# InputOutput.net
KiCad netlist of a schematic drawn in Altium Designer
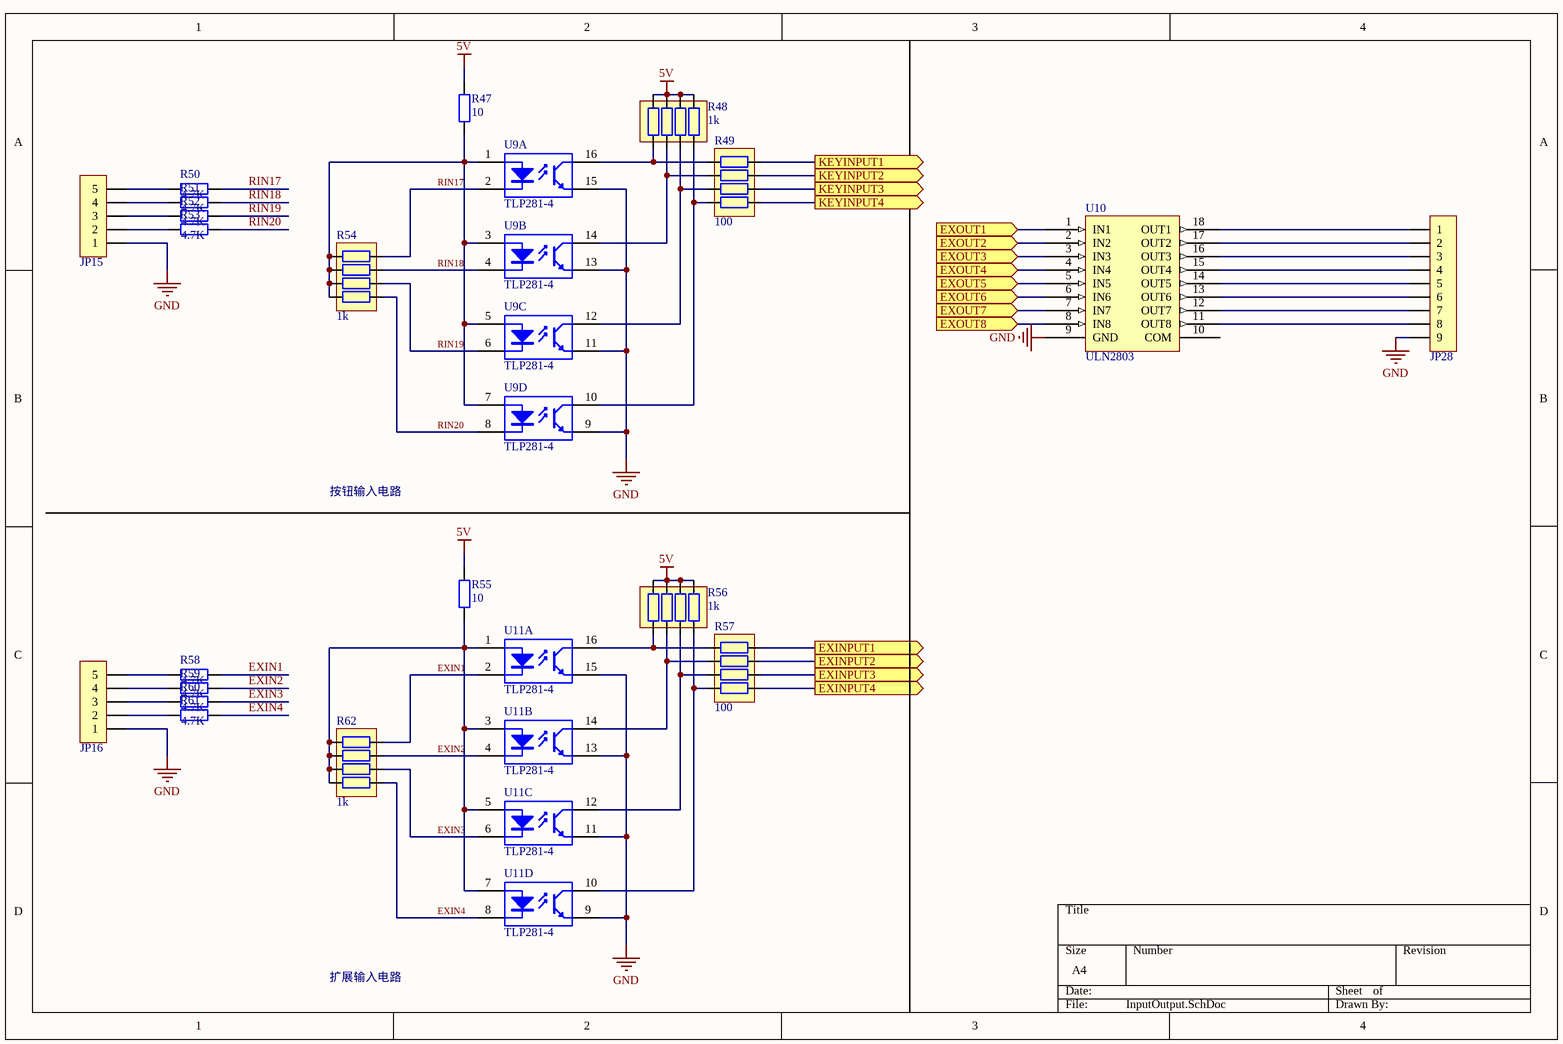
[diagram p0: InputOutput.SchDoc]

(export (version "E")
  (design (tool "Eeschema 10.0.6"))
  (components
    (comp (ref "JP15")
      (value "HDR-1X5")
      (footprint "XH2.54-LI-5P")
      (description "5P接插件")
      (libsource (lib "4.5   - 接插件-脚距2.54") (part "Header 5"))
    )
    (comp (ref "JP16")
      (value "HDR-1X5")
      (footprint "XH2.54-LI-5P")
      (description "5P接插件")
      (libsource (lib "4.5   - 接插件-脚距2.54") (part "Header 5"))
    )
    (comp (ref "JP28")
      (value "HDR-1X9")
      (footprint "XH2.54-LI-9P")
      (description "9P接插件")
      (libsource (lib "4.5   - 接插件-脚距2.54") (part "Header 9"))
    )
    (comp (ref "R47")
      (value "10")
      (footprint "R 0603_L")
      (description "贴片电阻")
      (libsource (lib "3.1   - 电阻-电容-电感") (part "R"))
    )
    (comp (ref "R48")
      (value "1k")
      (footprint "RCA-8P4R-0603")
      (description "贴片网络排阻")
      (libsource (lib "电阻-电容-电感") (part "R-8P4R"))
    )
    (comp (ref "R49")
      (value "100")
      (footprint "RCA-8P4R-0603")
      (description "贴片网络排阻")
      (libsource (lib "") (part "R-8P4R_1"))
    )
    (comp (ref "R50")
      (value "4.7K")
      (footprint "R 0603_L")
      (description "贴片电阻")
      (libsource (lib "3.1   - 电阻-电容-电感") (part "R"))
    )
    (comp (ref "R51")
      (value "4.7K")
      (footprint "R 0603_L")
      (description "贴片电阻")
      (libsource (lib "3.1   - 电阻-电容-电感") (part "R"))
    )
    (comp (ref "R52")
      (value "4.7K")
      (footprint "R 0603_L")
      (description "贴片电阻")
      (libsource (lib "3.1   - 电阻-电容-电感") (part "R"))
    )
    (comp (ref "R53")
      (value "4.7K")
      (footprint "R 0603_L")
      (description "贴片电阻")
      (libsource (lib "3.1   - 电阻-电容-电感") (part "R"))
    )
    (comp (ref "R54")
      (value "1k")
      (footprint "RCA-8P4R-0603")
      (description "贴片网络排阻")
      (libsource (lib "") (part "R-8P4R_2"))
    )
    (comp (ref "R55")
      (value "10")
      (footprint "R 0603_L")
      (description "贴片电阻")
      (libsource (lib "3.1   - 电阻-电容-电感") (part "R"))
    )
    (comp (ref "R56")
      (value "1k")
      (footprint "RCA-8P4R-0603")
      (description "贴片网络排阻")
      (libsource (lib "电阻-电容-电感") (part "R-8P4R"))
    )
    (comp (ref "R57")
      (value "100")
      (footprint "RCA-8P4R-0603")
      (description "贴片网络排阻")
      (libsource (lib "") (part "R-8P4R_1"))
    )
    (comp (ref "R58")
      (value "4.7K")
      (footprint "R 0603_L")
      (description "贴片电阻")
      (libsource (lib "3.1   - 电阻-电容-电感") (part "R"))
    )
    (comp (ref "R59")
      (value "4.7K")
      (footprint "R 0603_L")
      (description "贴片电阻")
      (libsource (lib "3.1   - 电阻-电容-电感") (part "R"))
    )
    (comp (ref "R60")
      (value "4.7K")
      (footprint "R 0603_L")
      (description "贴片电阻")
      (libsource (lib "3.1   - 电阻-电容-电感") (part "R"))
    )
    (comp (ref "R61")
      (value "4.7K")
      (footprint "R 0603_L")
      (description "贴片电阻")
      (libsource (lib "3.1   - 电阻-电容-电感") (part "R"))
    )
    (comp (ref "R62")
      (value "1k")
      (footprint "RCA-8P4R-0603")
      (description "贴片网络排阻")
      (libsource (lib "") (part "R-8P4R_2"))
    )
    (comp (ref "U9") (value "TLP281-4") (footprint "SOP16N_N") (libsource (lib "自编原件库") (part "TLP281-4")))
    (comp (ref "U10") (value "ULN2803") (footprint "SO-G18") (libsource (lib "总图") (part "ULN2803")))
    (comp (ref "U11") (value "TLP281-4") (footprint "SOP16N_N") (libsource (lib "自编原件库") (part "TLP281-4")))
  )
  (nets
    (net (code "1") (name "/EXIN1") (class "Default")
      (node (ref "R58") (pin "1") (pinfunction "1_1") (pintype "passive"))
      (node (ref "R62") (pin "8") (pinfunction "8_8") (pintype "passive"))
      (node (ref "U11") (pin "2") (pinfunction "2_2") (pintype "passive"))
    )
    (net (code "2") (name "/EXIN2") (class "Default")
      (node (ref "R59") (pin "1") (pinfunction "1_1") (pintype "passive"))
      (node (ref "R62") (pin "7") (pinfunction "7_7") (pintype "passive"))
      (node (ref "U11") (pin "4") (pinfunction "4_4") (pintype "passive"))
    )
    (net (code "3") (name "/EXIN3") (class "Default")
      (node (ref "R60") (pin "1") (pinfunction "1_1") (pintype "passive"))
      (node (ref "R62") (pin "6") (pinfunction "6_6") (pintype "passive"))
      (node (ref "U11") (pin "6") (pinfunction "6_6") (pintype "passive"))
    )
    (net (code "4") (name "/EXIN4") (class "Default")
      (node (ref "R61") (pin "1") (pinfunction "1_1") (pintype "passive"))
      (node (ref "R62") (pin "5") (pinfunction "5_5") (pintype "passive"))
      (node (ref "U11") (pin "8") (pinfunction "8_8") (pintype "passive"))
    )
    (net (code "5") (name "/EXINPUT1") (class "Default")
      (node (ref "R57") (pin "1") (pinfunction "1_1") (pintype "passive"))
    )
    (net (code "6") (name "/EXINPUT2") (class "Default")
      (node (ref "R57") (pin "2") (pinfunction "2_2") (pintype "passive"))
    )
    (net (code "7") (name "/EXINPUT3") (class "Default")
      (node (ref "R57") (pin "3") (pinfunction "3_3") (pintype "passive"))
    )
    (net (code "8") (name "/EXINPUT4") (class "Default")
      (node (ref "R57") (pin "4") (pinfunction "4_4") (pintype "passive"))
    )
    (net (code "9") (name "/EXOUT1") (class "Default")
      (node (ref "U10") (pin "1") (pinfunction "IN1_1") (pintype "input"))
    )
    (net (code "10") (name "/EXOUT2") (class "Default")
      (node (ref "U10") (pin "2") (pinfunction "IN2_2") (pintype "input"))
    )
    (net (code "11") (name "/EXOUT3") (class "Default")
      (node (ref "U10") (pin "3") (pinfunction "IN3_3") (pintype "input"))
    )
    (net (code "12") (name "/EXOUT4") (class "Default")
      (node (ref "U10") (pin "4") (pinfunction "IN4_4") (pintype "input"))
    )
    (net (code "13") (name "/EXOUT5") (class "Default")
      (node (ref "U10") (pin "5") (pinfunction "IN5_5") (pintype "input"))
    )
    (net (code "14") (name "/EXOUT6") (class "Default")
      (node (ref "U10") (pin "6") (pinfunction "IN6_6") (pintype "input"))
    )
    (net (code "15") (name "/EXOUT7") (class "Default")
      (node (ref "U10") (pin "7") (pinfunction "IN7_7") (pintype "input"))
    )
    (net (code "16") (name "/EXOUT8") (class "Default")
      (node (ref "U10") (pin "8") (pinfunction "IN8_8") (pintype "input"))
    )
    (net (code "17") (name "/KEYINPUT1") (class "Default")
      (node (ref "R49") (pin "1") (pinfunction "1_1") (pintype "passive"))
    )
    (net (code "18") (name "/KEYINPUT2") (class "Default")
      (node (ref "R49") (pin "2") (pinfunction "2_2") (pintype "passive"))
    )
    (net (code "19") (name "/KEYINPUT3") (class "Default")
      (node (ref "R49") (pin "3") (pinfunction "3_3") (pintype "passive"))
    )
    (net (code "20") (name "/KEYINPUT4") (class "Default")
      (node (ref "R49") (pin "4") (pinfunction "4_4") (pintype "passive"))
    )
    (net (code "21") (name "/RIN17") (class "Default")
      (node (ref "R50") (pin "1") (pinfunction "1_1") (pintype "passive"))
      (node (ref "R54") (pin "8") (pinfunction "8_8") (pintype "passive"))
      (node (ref "U9") (pin "2") (pinfunction "2_2") (pintype "passive"))
    )
    (net (code "22") (name "/RIN18") (class "Default")
      (node (ref "R51") (pin "1") (pinfunction "1_1") (pintype "passive"))
      (node (ref "R54") (pin "7") (pinfunction "7_7") (pintype "passive"))
      (node (ref "U9") (pin "4") (pinfunction "4_4") (pintype "passive"))
    )
    (net (code "23") (name "/RIN19") (class "Default")
      (node (ref "R52") (pin "1") (pinfunction "1_1") (pintype "passive"))
      (node (ref "R54") (pin "6") (pinfunction "6_6") (pintype "passive"))
      (node (ref "U9") (pin "6") (pinfunction "6_6") (pintype "passive"))
    )
    (net (code "24") (name "/RIN20") (class "Default")
      (node (ref "R53") (pin "1") (pinfunction "1_1") (pintype "passive"))
      (node (ref "R54") (pin "5") (pinfunction "5_5") (pintype "passive"))
      (node (ref "U9") (pin "8") (pinfunction "8_8") (pintype "passive"))
    )
    (net (code "25") (name "5V") (class "Default")
      (node (ref "R47") (pin "1") (pinfunction "1_1") (pintype "passive"))
      (node (ref "R48") (pin "5") (pinfunction "5_5") (pintype "passive"))
      (node (ref "R48") (pin "6") (pinfunction "6_6") (pintype "passive"))
      (node (ref "R48") (pin "7") (pinfunction "7_7") (pintype "passive"))
      (node (ref "R48") (pin "8") (pinfunction "8_8") (pintype "passive"))
      (node (ref "R55") (pin "1") (pinfunction "1_1") (pintype "passive"))
      (node (ref "R56") (pin "5") (pinfunction "5_5") (pintype "passive"))
      (node (ref "R56") (pin "6") (pinfunction "6_6") (pintype "passive"))
      (node (ref "R56") (pin "7") (pinfunction "7_7") (pintype "passive"))
      (node (ref "R56") (pin "8") (pinfunction "8_8") (pintype "passive"))
    )
    (net (code "26") (name "GND") (class "Default")
      (node (ref "JP15") (pin "1") (pinfunction "1_1") (pintype "passive"))
      (node (ref "JP16") (pin "1") (pinfunction "1_1") (pintype "passive"))
      (node (ref "JP28") (pin "9") (pinfunction "9_9") (pintype "passive"))
      (node (ref "U10") (pin "9") (pinfunction "GND_9") (pintype "passive"))
      (node (ref "U11") (pin "11") (pinfunction "11_11") (pintype "passive"))
      (node (ref "U11") (pin "13") (pinfunction "13_13") (pintype "passive"))
      (node (ref "U11") (pin "15") (pinfunction "15_15") (pintype "passive"))
      (node (ref "U11") (pin "9") (pinfunction "9_9") (pintype "passive"))
      (node (ref "U9") (pin "11") (pinfunction "11_11") (pintype "passive"))
      (node (ref "U9") (pin "13") (pinfunction "13_13") (pintype "passive"))
      (node (ref "U9") (pin "15") (pinfunction "15_15") (pintype "passive"))
      (node (ref "U9") (pin "9") (pinfunction "9_9") (pintype "passive"))
    )
    (net (code "27") (name "Net-(JP15-Pad2)") (class "Default")
      (node (ref "JP15") (pin "2") (pinfunction "2_2") (pintype "passive"))
      (node (ref "R53") (pin "2") (pinfunction "2_2") (pintype "passive"))
    )
    (net (code "28") (name "Net-(JP15-Pad3)") (class "Default")
      (node (ref "JP15") (pin "3") (pinfunction "3_3") (pintype "passive"))
      (node (ref "R52") (pin "2") (pinfunction "2_2") (pintype "passive"))
    )
    (net (code "29") (name "Net-(JP15-Pad4)") (class "Default")
      (node (ref "JP15") (pin "4") (pinfunction "4_4") (pintype "passive"))
      (node (ref "R51") (pin "2") (pinfunction "2_2") (pintype "passive"))
    )
    (net (code "30") (name "Net-(JP15-Pad5)") (class "Default")
      (node (ref "JP15") (pin "5") (pinfunction "5_5") (pintype "passive"))
      (node (ref "R50") (pin "2") (pinfunction "2_2") (pintype "passive"))
    )
    (net (code "31") (name "Net-(JP16-Pad2)") (class "Default")
      (node (ref "JP16") (pin "2") (pinfunction "2_2") (pintype "passive"))
      (node (ref "R61") (pin "2") (pinfunction "2_2") (pintype "passive"))
    )
    (net (code "32") (name "Net-(JP16-Pad3)") (class "Default")
      (node (ref "JP16") (pin "3") (pinfunction "3_3") (pintype "passive"))
      (node (ref "R60") (pin "2") (pinfunction "2_2") (pintype "passive"))
    )
    (net (code "33") (name "Net-(JP16-Pad4)") (class "Default")
      (node (ref "JP16") (pin "4") (pinfunction "4_4") (pintype "passive"))
      (node (ref "R59") (pin "2") (pinfunction "2_2") (pintype "passive"))
    )
    (net (code "34") (name "Net-(JP16-Pad5)") (class "Default")
      (node (ref "JP16") (pin "5") (pinfunction "5_5") (pintype "passive"))
      (node (ref "R58") (pin "2") (pinfunction "2_2") (pintype "passive"))
    )
    (net (code "35") (name "Net-(R47-Pad2)") (class "Default")
      (node (ref "R47") (pin "2") (pinfunction "2_2") (pintype "passive"))
      (node (ref "R54") (pin "1") (pinfunction "1_1") (pintype "passive"))
      (node (ref "R54") (pin "2") (pinfunction "2_2") (pintype "passive"))
      (node (ref "R54") (pin "3") (pinfunction "3_3") (pintype "passive"))
      (node (ref "R54") (pin "4") (pinfunction "4_4") (pintype "passive"))
      (node (ref "U9") (pin "1") (pinfunction "1_1") (pintype "passive"))
      (node (ref "U9") (pin "3") (pinfunction "3_3") (pintype "passive"))
      (node (ref "U9") (pin "5") (pinfunction "5_5") (pintype "passive"))
      (node (ref "U9") (pin "7") (pinfunction "7_7") (pintype "passive"))
    )
    (net (code "36") (name "Net-(R48-Pad1)") (class "Default")
      (node (ref "R48") (pin "1") (pinfunction "1_1") (pintype "passive"))
      (node (ref "R49") (pin "8") (pinfunction "8_8") (pintype "passive"))
      (node (ref "U9") (pin "16") (pinfunction "16_16") (pintype "passive"))
    )
    (net (code "37") (name "Net-(R48-Pad2)") (class "Default")
      (node (ref "R48") (pin "2") (pinfunction "2_2") (pintype "passive"))
      (node (ref "R49") (pin "7") (pinfunction "7_7") (pintype "passive"))
      (node (ref "U9") (pin "14") (pinfunction "14_14") (pintype "passive"))
    )
    (net (code "38") (name "Net-(R48-Pad3)") (class "Default")
      (node (ref "R48") (pin "3") (pinfunction "3_3") (pintype "passive"))
      (node (ref "R49") (pin "6") (pinfunction "6_6") (pintype "passive"))
      (node (ref "U9") (pin "12") (pinfunction "12_12") (pintype "passive"))
    )
    (net (code "39") (name "Net-(R48-Pad4)") (class "Default")
      (node (ref "R48") (pin "4") (pinfunction "4_4") (pintype "passive"))
      (node (ref "R49") (pin "5") (pinfunction "5_5") (pintype "passive"))
      (node (ref "U9") (pin "10") (pinfunction "10_10") (pintype "passive"))
    )
    (net (code "40") (name "Net-(R55-Pad2)") (class "Default")
      (node (ref "R55") (pin "2") (pinfunction "2_2") (pintype "passive"))
      (node (ref "R62") (pin "1") (pinfunction "1_1") (pintype "passive"))
      (node (ref "R62") (pin "2") (pinfunction "2_2") (pintype "passive"))
      (node (ref "R62") (pin "3") (pinfunction "3_3") (pintype "passive"))
      (node (ref "R62") (pin "4") (pinfunction "4_4") (pintype "passive"))
      (node (ref "U11") (pin "1") (pinfunction "1_1") (pintype "passive"))
      (node (ref "U11") (pin "3") (pinfunction "3_3") (pintype "passive"))
      (node (ref "U11") (pin "5") (pinfunction "5_5") (pintype "passive"))
      (node (ref "U11") (pin "7") (pinfunction "7_7") (pintype "passive"))
    )
    (net (code "41") (name "Net-(R56-Pad1)") (class "Default")
      (node (ref "R56") (pin "1") (pinfunction "1_1") (pintype "passive"))
      (node (ref "R57") (pin "8") (pinfunction "8_8") (pintype "passive"))
      (node (ref "U11") (pin "16") (pinfunction "16_16") (pintype "passive"))
    )
    (net (code "42") (name "Net-(R56-Pad2)") (class "Default")
      (node (ref "R56") (pin "2") (pinfunction "2_2") (pintype "passive"))
      (node (ref "R57") (pin "7") (pinfunction "7_7") (pintype "passive"))
      (node (ref "U11") (pin "14") (pinfunction "14_14") (pintype "passive"))
    )
    (net (code "43") (name "Net-(R56-Pad3)") (class "Default")
      (node (ref "R56") (pin "3") (pinfunction "3_3") (pintype "passive"))
      (node (ref "R57") (pin "6") (pinfunction "6_6") (pintype "passive"))
      (node (ref "U11") (pin "12") (pinfunction "12_12") (pintype "passive"))
    )
    (net (code "44") (name "Net-(R56-Pad4)") (class "Default")
      (node (ref "R56") (pin "4") (pinfunction "4_4") (pintype "passive"))
      (node (ref "R57") (pin "5") (pinfunction "5_5") (pintype "passive"))
      (node (ref "U11") (pin "10") (pinfunction "10_10") (pintype "passive"))
    )
    (net (code "45") (name "Net-(U10-OUT1)") (class "Default")
      (node (ref "JP28") (pin "1") (pinfunction "1_1") (pintype "passive"))
      (node (ref "U10") (pin "18") (pinfunction "OUT1_18") (pintype "output"))
    )
    (net (code "46") (name "Net-(U10-OUT2)") (class "Default")
      (node (ref "JP28") (pin "2") (pinfunction "2_2") (pintype "passive"))
      (node (ref "U10") (pin "17") (pinfunction "OUT2_17") (pintype "output"))
    )
    (net (code "47") (name "Net-(U10-OUT3)") (class "Default")
      (node (ref "JP28") (pin "3") (pinfunction "3_3") (pintype "passive"))
      (node (ref "U10") (pin "16") (pinfunction "OUT3_16") (pintype "output"))
    )
    (net (code "48") (name "Net-(U10-OUT4)") (class "Default")
      (node (ref "JP28") (pin "4") (pinfunction "4_4") (pintype "passive"))
      (node (ref "U10") (pin "15") (pinfunction "OUT4_15") (pintype "output"))
    )
    (net (code "49") (name "Net-(U10-OUT5)") (class "Default")
      (node (ref "JP28") (pin "5") (pinfunction "5_5") (pintype "passive"))
      (node (ref "U10") (pin "14") (pinfunction "OUT5_14") (pintype "output"))
    )
    (net (code "50") (name "Net-(U10-OUT6)") (class "Default")
      (node (ref "JP28") (pin "6") (pinfunction "6_6") (pintype "passive"))
      (node (ref "U10") (pin "13") (pinfunction "OUT6_13") (pintype "output"))
    )
    (net (code "51") (name "Net-(U10-OUT7)") (class "Default")
      (node (ref "JP28") (pin "7") (pinfunction "7_7") (pintype "passive"))
      (node (ref "U10") (pin "12") (pinfunction "OUT7_12") (pintype "output"))
    )
    (net (code "52") (name "Net-(U10-OUT8)") (class "Default")
      (node (ref "JP28") (pin "8") (pinfunction "8_8") (pintype "passive"))
      (node (ref "U10") (pin "11") (pinfunction "OUT8_11") (pintype "output"))
    )
    (net (code "53") (name "unconnected-(U10-COM-Pad10)") (class "Default")
      (node (ref "U10") (pin "10") (pinfunction "COM_10") (pintype "power_in"))
    )
  )
)
